# STM.net
KiCad netlist of a schematic drawn in Altium Designer
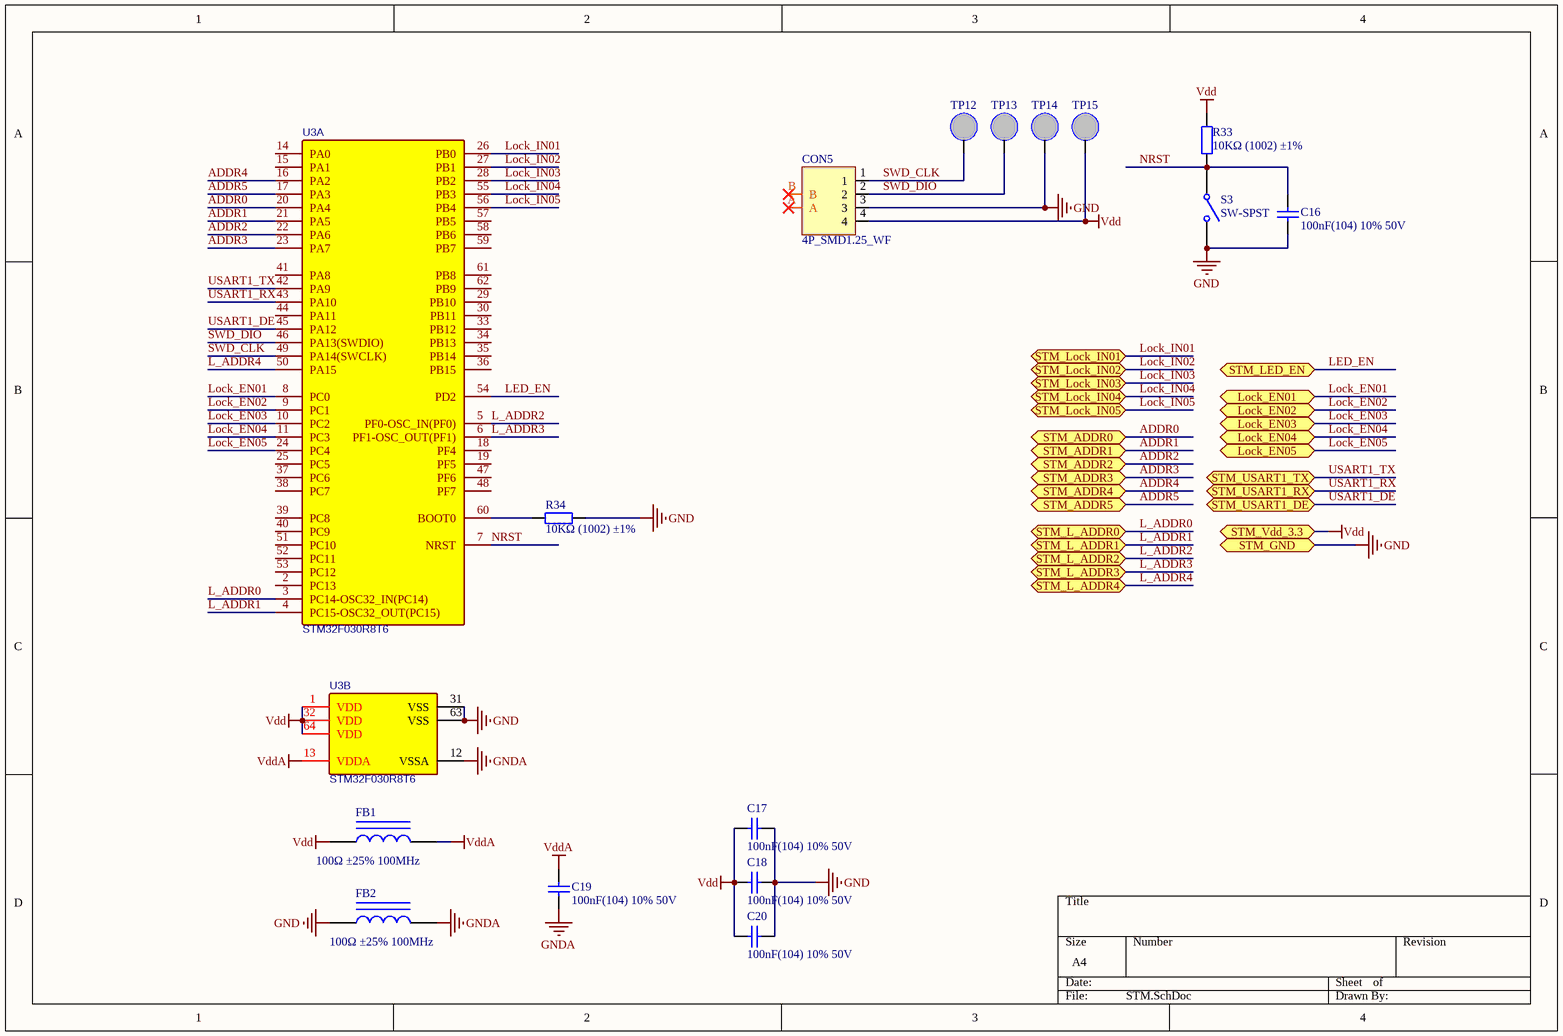
[diagram p0: STM.SchDoc]

(export (version "E")
  (design (tool "Eeschema 10.0.6"))
  (components
    (comp (ref "C16")
      (value "100nF(104) 10% 50V")
      (footprint "0805_C")
      (description "贴片电容")
      (libsource (lib "Miscellaneous Devices LC") (part "0805 100nF(104) 10% 50V"))
    )
    (comp (ref "C17")
      (value "100nF(104) 10% 50V")
      (footprint "0805_C")
      (description "贴片电容")
      (libsource (lib "Miscellaneous Devices LC") (part "0805 100nF(104) 10% 50V"))
    )
    (comp (ref "C18")
      (value "100nF(104) 10% 50V")
      (footprint "0805_C")
      (description "贴片电容")
      (libsource (lib "Miscellaneous Devices LC") (part "0805 100nF(104) 10% 50V"))
    )
    (comp (ref "C19")
      (value "100nF(104) 10% 50V")
      (footprint "0805_C")
      (description "贴片电容")
      (libsource (lib "Miscellaneous Devices LC") (part "0805 100nF(104) 10% 50V"))
    )
    (comp (ref "C20")
      (value "100nF(104) 10% 50V")
      (footprint "0805_C")
      (description "贴片电容")
      (libsource (lib "Miscellaneous Devices LC") (part "0805 100nF(104) 10% 50V"))
    )
    (comp (ref "CON5")
      (value "4P_SMD1.25_WF")
      (footprint "MX 1.25-LS-4P")
      (libsource (lib "mylib") (part "4P_XH2.54_W"))
    )
    (comp (ref "FB1")
      (value "100Ω ±25% 100MHz")
      (footprint "0805_L")
      (description "贴片磁珠")
      (libsource (lib "Miscellaneous Devices LC") (part "0805 100Ω 25% 100MHz"))
    )
    (comp (ref "FB2")
      (value "100Ω ±25% 100MHz")
      (footprint "0805_L")
      (description "贴片磁珠")
      (libsource (lib "Miscellaneous Devices LC") (part "0805 100Ω 25% 100MHz"))
    )
    (comp (ref "R33")
      (value "10KΩ (1002) ±1%")
      (footprint "0805_R")
      (description "贴片电阻")
      (libsource (lib "") (part "0805 10KΩ (1002) 1%_1"))
    )
    (comp (ref "R34")
      (value "10KΩ (1002) ±1%")
      (footprint "0805_R")
      (description "贴片电阻")
      (libsource (lib "Miscellaneous Devices LC") (part "0805 10KΩ (1002) 1%"))
    )
    (comp (ref "S3")
      (value "SW-SPST")
      (footprint "key")
      (description "Single-Pole, Single-Throw Switch")
      (fields (field (name "PUBLISHER") "Altium Limited"))
      (libsource (lib "Miscellaneous Devices") (part "SW-SPST"))
    )
    (comp (ref "TP12") (value "TP") (footprint "TP") (libsource (lib "mylib") (part "TP")))
    (comp (ref "TP13") (value "TP") (footprint "TP") (libsource (lib "mylib") (part "TP")))
    (comp (ref "TP14") (value "TP") (footprint "TP") (libsource (lib "mylib") (part "TP")))
    (comp (ref "TP15") (value "TP") (footprint "TP") (libsource (lib "mylib") (part "TP")))
    (comp (ref "U3")
      (value "STM32F030R8T6")
      (footprint "LQFP-64_10X10X05P")
      (fields (field (name "BOM_SUPPLIER PART") "C39105") (field (name "SUBPART_NO") "1"))
      (libsource (lib "mylib") (part "STM32F030R8T6"))
    )
  )
  (nets
    (net (code "1") (name "/ADDR0") (class "Default")
      (node (ref "U3") (pin "20") (pinfunction "PA4_20") (pintype "passive"))
    )
    (net (code "2") (name "/ADDR1") (class "Default")
      (node (ref "U3") (pin "21") (pinfunction "PA5_21") (pintype "passive"))
    )
    (net (code "3") (name "/ADDR2") (class "Default")
      (node (ref "U3") (pin "22") (pinfunction "PA6_22") (pintype "passive"))
    )
    (net (code "4") (name "/ADDR3") (class "Default")
      (node (ref "U3") (pin "23") (pinfunction "PA7_23") (pintype "passive"))
    )
    (net (code "5") (name "/ADDR4") (class "Default")
      (node (ref "U3") (pin "16") (pinfunction "PA2_16") (pintype "passive"))
    )
    (net (code "6") (name "/ADDR5") (class "Default")
      (node (ref "U3") (pin "17") (pinfunction "PA3_17") (pintype "passive"))
    )
    (net (code "7") (name "/LED_EN") (class "Default")
      (node (ref "U3") (pin "54") (pinfunction "PD2_54") (pintype "passive"))
    )
    (net (code "8") (name "/L_ADDR0") (class "Default")
      (node (ref "U3") (pin "3") (pinfunction "PC14-OSC32_IN(PC14)_3") (pintype "passive"))
    )
    (net (code "9") (name "/L_ADDR1") (class "Default")
      (node (ref "U3") (pin "4") (pinfunction "PC15-OSC32_OUT(PC15)_4") (pintype "passive"))
    )
    (net (code "10") (name "/L_ADDR2") (class "Default")
      (node (ref "U3") (pin "5") (pinfunction "PF0-OSC_IN(PF0)_5") (pintype "passive"))
    )
    (net (code "11") (name "/L_ADDR3") (class "Default")
      (node (ref "U3") (pin "6") (pinfunction "PF1-OSC_OUT(PF1)_6") (pintype "passive"))
    )
    (net (code "12") (name "/L_ADDR4") (class "Default")
      (node (ref "U3") (pin "50") (pinfunction "PA15_50") (pintype "passive"))
    )
    (net (code "13") (name "/Lock_EN01") (class "Default")
      (node (ref "U3") (pin "8") (pinfunction "PC0_8") (pintype "passive"))
    )
    (net (code "14") (name "/Lock_EN02") (class "Default")
      (node (ref "U3") (pin "9") (pinfunction "PC1_9") (pintype "passive"))
    )
    (net (code "15") (name "/Lock_EN03") (class "Default")
      (node (ref "U3") (pin "10") (pinfunction "PC2_10") (pintype "passive"))
    )
    (net (code "16") (name "/Lock_EN04") (class "Default")
      (node (ref "U3") (pin "11") (pinfunction "PC3_11") (pintype "passive"))
    )
    (net (code "17") (name "/Lock_EN05") (class "Default")
      (node (ref "U3") (pin "24") (pinfunction "PC4_24") (pintype "passive"))
    )
    (net (code "18") (name "/Lock_IN01") (class "Default")
      (node (ref "U3") (pin "26") (pinfunction "PB0_26") (pintype "passive"))
    )
    (net (code "19") (name "/Lock_IN02") (class "Default")
      (node (ref "U3") (pin "27") (pinfunction "PB1_27") (pintype "passive"))
    )
    (net (code "20") (name "/Lock_IN03") (class "Default")
      (node (ref "U3") (pin "28") (pinfunction "PB2_28") (pintype "passive"))
    )
    (net (code "21") (name "/Lock_IN04") (class "Default")
      (node (ref "U3") (pin "55") (pinfunction "PB3_55") (pintype "passive"))
    )
    (net (code "22") (name "/Lock_IN05") (class "Default")
      (node (ref "U3") (pin "56") (pinfunction "PB4_56") (pintype "passive"))
    )
    (net (code "23") (name "/NRST") (class "Default")
      (node (ref "C16") (pin "2") (pinfunction "2_2") (pintype "passive"))
      (node (ref "R33") (pin "1") (pinfunction "1_1") (pintype "passive"))
      (node (ref "S3") (pin "1") (pinfunction "COMMON_1") (pintype "passive"))
      (node (ref "U3") (pin "7") (pinfunction "NRST_7") (pintype "passive"))
    )
    (net (code "24") (name "/SWD_CLK") (class "Default")
      (node (ref "CON5") (pin "1") (pinfunction "1_1") (pintype "passive"))
      (node (ref "TP12") (pin "1") (pinfunction "1_1") (pintype "passive"))
      (node (ref "U3") (pin "49") (pinfunction "PA14(SWCLK)_49") (pintype "passive"))
    )
    (net (code "25") (name "/SWD_DIO") (class "Default")
      (node (ref "CON5") (pin "2") (pinfunction "2_2") (pintype "passive"))
      (node (ref "TP13") (pin "1") (pinfunction "1_1") (pintype "passive"))
      (node (ref "U3") (pin "46") (pinfunction "PA13(SWDIO)_46") (pintype "passive"))
    )
    (net (code "26") (name "/USART1_DE") (class "Default")
      (node (ref "U3") (pin "45") (pinfunction "PA12_45") (pintype "passive"))
    )
    (net (code "27") (name "/USART1_RX") (class "Default")
      (node (ref "U3") (pin "43") (pinfunction "PA10_43") (pintype "passive"))
    )
    (net (code "28") (name "/USART1_TX") (class "Default")
      (node (ref "U3") (pin "42") (pinfunction "PA9_42") (pintype "passive"))
    )
    (net (code "29") (name "GND") (class "Default")
      (node (ref "C16") (pin "1") (pinfunction "1_1") (pintype "passive"))
      (node (ref "C17") (pin "1") (pinfunction "1_1") (pintype "passive"))
      (node (ref "C18") (pin "1") (pinfunction "1_1") (pintype "passive"))
      (node (ref "C20") (pin "1") (pinfunction "1_1") (pintype "passive"))
      (node (ref "CON5") (pin "3") (pinfunction "3_3") (pintype "passive"))
      (node (ref "FB2") (pin "1") (pinfunction "1_1") (pintype "passive"))
      (node (ref "R34") (pin "2") (pinfunction "2_2") (pintype "passive"))
      (node (ref "S3") (pin "2") (pinfunction "NO_2") (pintype "passive"))
      (node (ref "TP14") (pin "1") (pinfunction "1_1") (pintype "passive"))
      (node (ref "U3") (pin "31") (pinfunction "VSS_31") (pintype "passive"))
      (node (ref "U3") (pin "63") (pinfunction "VSS_63") (pintype "passive"))
    )
    (net (code "30") (name "GNDA") (class "Default")
      (node (ref "C19") (pin "1") (pinfunction "1_1") (pintype "passive"))
      (node (ref "FB2") (pin "2") (pinfunction "2_2") (pintype "passive"))
      (node (ref "U3") (pin "12") (pinfunction "VSSA_12") (pintype "passive"))
    )
    (net (code "31") (name "Net-(U3A-BOOT0)") (class "Default")
      (node (ref "R34") (pin "1") (pinfunction "1_1") (pintype "passive"))
      (node (ref "U3") (pin "60") (pinfunction "BOOT0_60") (pintype "passive"))
    )
    (net (code "32") (name "Vdd") (class "Default")
      (node (ref "C17") (pin "2") (pinfunction "2_2") (pintype "passive"))
      (node (ref "C18") (pin "2") (pinfunction "2_2") (pintype "passive"))
      (node (ref "C20") (pin "2") (pinfunction "2_2") (pintype "passive"))
      (node (ref "CON5") (pin "4") (pinfunction "4_4") (pintype "passive"))
      (node (ref "FB1") (pin "1") (pinfunction "1_1") (pintype "passive"))
      (node (ref "R33") (pin "2") (pinfunction "2_2") (pintype "passive"))
      (node (ref "TP15") (pin "1") (pinfunction "1_1") (pintype "passive"))
      (node (ref "U3") (pin "1") (pinfunction "VDD_1") (pintype "passive"))
      (node (ref "U3") (pin "32") (pinfunction "VDD_32") (pintype "passive"))
      (node (ref "U3") (pin "64") (pinfunction "VDD_64") (pintype "passive"))
    )
    (net (code "33") (name "VddA") (class "Default")
      (node (ref "C19") (pin "2") (pinfunction "2_2") (pintype "passive"))
      (node (ref "FB1") (pin "2") (pinfunction "2_2") (pintype "passive"))
      (node (ref "U3") (pin "13") (pinfunction "VDDA_13") (pintype "passive"))
    )
    (net (code "34") (name "unconnected-(CON5-PadA)") (class "Default")
      (node (ref "CON5") (pin "A") (pinfunction "A_A") (pintype "passive+no_connect"))
    )
    (net (code "35") (name "unconnected-(CON5-PadB)") (class "Default")
      (node (ref "CON5") (pin "B") (pinfunction "B_B") (pintype "passive+no_connect"))
    )
    (net (code "36") (name "unconnected-(U3A-PA0-Pad14)") (class "Default")
      (node (ref "U3") (pin "14") (pinfunction "PA0_14") (pintype "passive"))
    )
    (net (code "37") (name "unconnected-(U3A-PA1-Pad15)") (class "Default")
      (node (ref "U3") (pin "15") (pinfunction "PA1_15") (pintype "passive"))
    )
    (net (code "38") (name "unconnected-(U3A-PA8-Pad41)") (class "Default")
      (node (ref "U3") (pin "41") (pinfunction "PA8_41") (pintype "passive"))
    )
    (net (code "39") (name "unconnected-(U3A-PA11-Pad44)") (class "Default")
      (node (ref "U3") (pin "44") (pinfunction "PA11_44") (pintype "passive"))
    )
    (net (code "40") (name "unconnected-(U3A-PB5-Pad57)") (class "Default")
      (node (ref "U3") (pin "57") (pinfunction "PB5_57") (pintype "passive"))
    )
    (net (code "41") (name "unconnected-(U3A-PB6-Pad58)") (class "Default")
      (node (ref "U3") (pin "58") (pinfunction "PB6_58") (pintype "passive"))
    )
    (net (code "42") (name "unconnected-(U3A-PB7-Pad59)") (class "Default")
      (node (ref "U3") (pin "59") (pinfunction "PB7_59") (pintype "passive"))
    )
    (net (code "43") (name "unconnected-(U3A-PB8-Pad61)") (class "Default")
      (node (ref "U3") (pin "61") (pinfunction "PB8_61") (pintype "passive"))
    )
    (net (code "44") (name "unconnected-(U3A-PB9-Pad62)") (class "Default")
      (node (ref "U3") (pin "62") (pinfunction "PB9_62") (pintype "passive"))
    )
    (net (code "45") (name "unconnected-(U3A-PB10-Pad29)") (class "Default")
      (node (ref "U3") (pin "29") (pinfunction "PB10_29") (pintype "passive"))
    )
    (net (code "46") (name "unconnected-(U3A-PB11-Pad30)") (class "Default")
      (node (ref "U3") (pin "30") (pinfunction "PB11_30") (pintype "passive"))
    )
    (net (code "47") (name "unconnected-(U3A-PB12-Pad33)") (class "Default")
      (node (ref "U3") (pin "33") (pinfunction "PB12_33") (pintype "passive"))
    )
    (net (code "48") (name "unconnected-(U3A-PB13-Pad34)") (class "Default")
      (node (ref "U3") (pin "34") (pinfunction "PB13_34") (pintype "passive"))
    )
    (net (code "49") (name "unconnected-(U3A-PB14-Pad35)") (class "Default")
      (node (ref "U3") (pin "35") (pinfunction "PB14_35") (pintype "passive"))
    )
    (net (code "50") (name "unconnected-(U3A-PB15-Pad36)") (class "Default")
      (node (ref "U3") (pin "36") (pinfunction "PB15_36") (pintype "passive"))
    )
    (net (code "51") (name "unconnected-(U3A-PC5-Pad25)") (class "Default")
      (node (ref "U3") (pin "25") (pinfunction "PC5_25") (pintype "passive"))
    )
    (net (code "52") (name "unconnected-(U3A-PC6-Pad37)") (class "Default")
      (node (ref "U3") (pin "37") (pinfunction "PC6_37") (pintype "passive"))
    )
    (net (code "53") (name "unconnected-(U3A-PC7-Pad38)") (class "Default")
      (node (ref "U3") (pin "38") (pinfunction "PC7_38") (pintype "passive"))
    )
    (net (code "54") (name "unconnected-(U3A-PC8-Pad39)") (class "Default")
      (node (ref "U3") (pin "39") (pinfunction "PC8_39") (pintype "passive"))
    )
    (net (code "55") (name "unconnected-(U3A-PC9-Pad40)") (class "Default")
      (node (ref "U3") (pin "40") (pinfunction "PC9_40") (pintype "passive"))
    )
    (net (code "56") (name "unconnected-(U3A-PC10-Pad51)") (class "Default")
      (node (ref "U3") (pin "51") (pinfunction "PC10_51") (pintype "passive"))
    )
    (net (code "57") (name "unconnected-(U3A-PC11-Pad52)") (class "Default")
      (node (ref "U3") (pin "52") (pinfunction "PC11_52") (pintype "passive"))
    )
    (net (code "58") (name "unconnected-(U3A-PC12-Pad53)") (class "Default")
      (node (ref "U3") (pin "53") (pinfunction "PC12_53") (pintype "passive"))
    )
    (net (code "59") (name "unconnected-(U3A-PC13-Pad2)") (class "Default")
      (node (ref "U3") (pin "2") (pinfunction "PC13_2") (pintype "passive"))
    )
    (net (code "60") (name "unconnected-(U3A-PF4-Pad18)") (class "Default")
      (node (ref "U3") (pin "18") (pinfunction "PF4_18") (pintype "passive"))
    )
    (net (code "61") (name "unconnected-(U3A-PF5-Pad19)") (class "Default")
      (node (ref "U3") (pin "19") (pinfunction "PF5_19") (pintype "passive"))
    )
    (net (code "62") (name "unconnected-(U3A-PF6-Pad47)") (class "Default")
      (node (ref "U3") (pin "47") (pinfunction "PF6_47") (pintype "passive"))
    )
    (net (code "63") (name "unconnected-(U3A-PF7-Pad48)") (class "Default")
      (node (ref "U3") (pin "48") (pinfunction "PF7_48") (pintype "passive"))
    )
  )
)
